# m80-v0_50.net
KiCad netlist of a schematic drawn in EAGLE
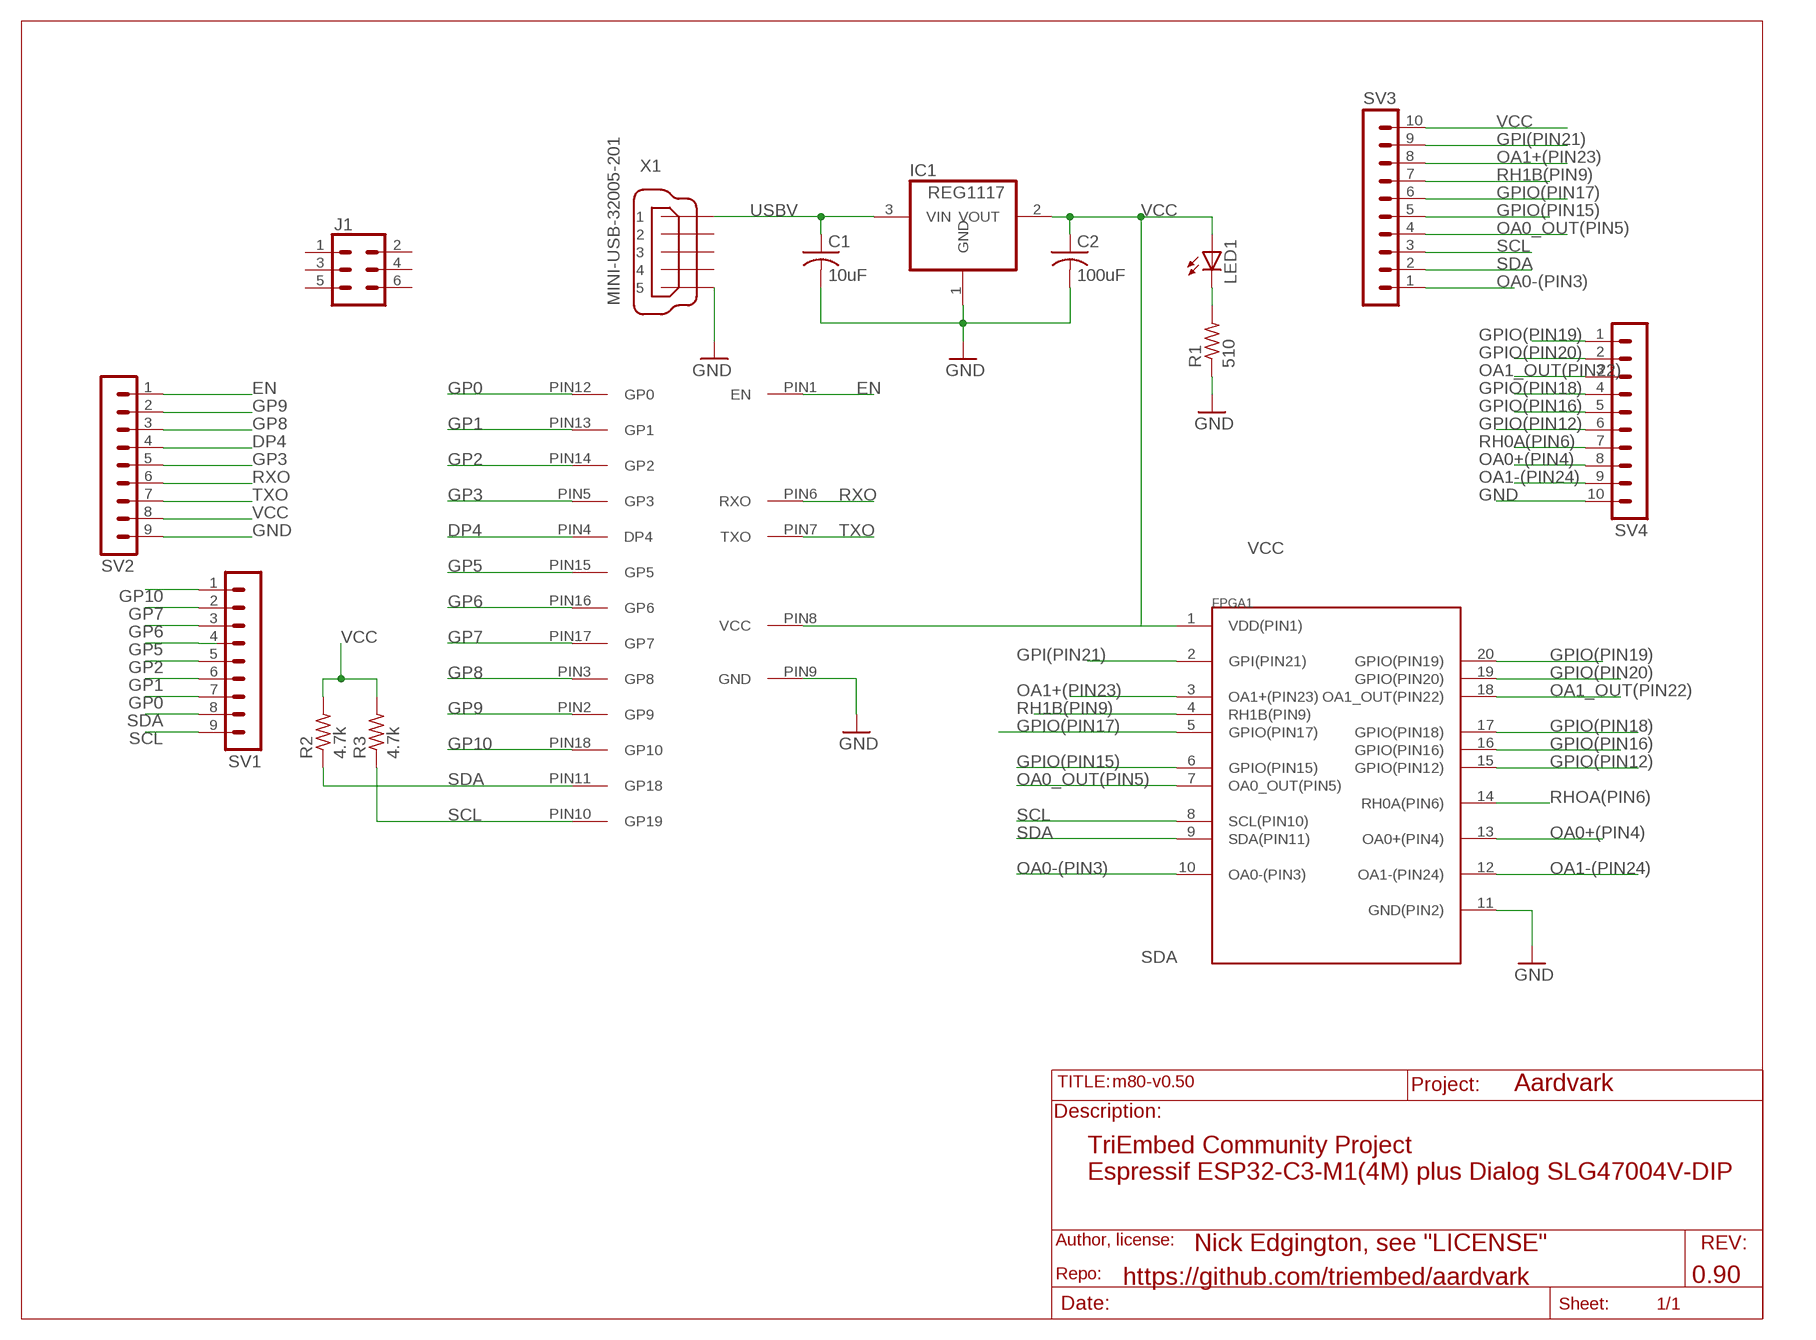
[diagram p0: schematic, sheet 1]

(export (version "E")
  (design (tool "Eeschema 10.0.6"))
  (components
    (comp (ref "C1")
      (value "10uF")
      (footprint "eagle-import:C0805")
      (libsource (lib "eagle-import") (part "C-USC0805"))
    )
    (comp (ref "C2")
      (value "100uF")
      (footprint "eagle-import:C1206")
      (libsource (lib "eagle-import") (part "C-USC1206"))
    )
    (comp (ref "FPGA1")
      (value "SLG7004V_DIP")
      (footprint "eagle-import:SLG47004V-DIP")
      (libsource (lib "eagle-import") (part "SLG7004V_DIP"))
    )
    (comp (ref "IC1")
      (value "REG1117")
      (footprint "eagle-import:SOT223")
      (libsource (lib "eagle-import") (part "REG1117"))
    )
    (comp (ref "J1")
      (value "CONN_03X2NO_SILK")
      (footprint "eagle-import:2X3-NS")
      (libsource (lib "eagle-import") (part "CONN_03X2NO_SILK"))
    )
    (comp (ref "LED1")
      (value "LEDCHIP-LED0805")
      (footprint "eagle-import:CHIP-LED0805")
      (libsource (lib "eagle-import") (part "LEDCHIP-LED0805"))
    )
    (comp (ref "R1")
      (value "510")
      (footprint "eagle-import:R0805")
      (libsource (lib "eagle-import") (part "R-US_R0805"))
    )
    (comp (ref "R2")
      (value "4.7k")
      (footprint "eagle-import:R0805")
      (libsource (lib "eagle-import") (part "R-US_R0805"))
    )
    (comp (ref "R3")
      (value "4.7k")
      (footprint "eagle-import:R0805")
      (libsource (lib "eagle-import") (part "R-US_R0805"))
    )
    (comp (ref "SV1")
      (value "MA09-1")
      (footprint "eagle-import:MA09-1")
      (libsource (lib "eagle-import") (part "MA09-1"))
    )
    (comp (ref "SV2")
      (value "MA09-1")
      (footprint "eagle-import:MA09-1")
      (libsource (lib "eagle-import") (part "MA09-1"))
    )
    (comp (ref "SV3")
      (value "MA10-1")
      (footprint "eagle-import:MA10-1")
      (libsource (lib "eagle-import") (part "MA10-1"))
    )
    (comp (ref "SV4")
      (value "MA10-1")
      (footprint "eagle-import:MA10-1")
      (libsource (lib "eagle-import") (part "MA10-1"))
    )
    (comp (ref "U$2")
      (value "UNTITLED_ESP32C3")
      (footprint "eagle-import:UNTITLED_ESP32-C3-01M")
      (libsource (lib "eagle-import") (part "UNTITLED_ESP32C3"))
    )
    (comp (ref "X1")
      (value "MINI-USB-32005-201")
      (footprint "eagle-import:32005-201")
      (libsource (lib "eagle-import") (part "MINI-USB-32005-201"))
    )
  )
  (nets
    (net (code "1") (name "/DP4") (class "Default")
      (node (ref "SV2") (pin "4") (pinfunction "4_4") (pintype "passive"))
      (node (ref "U$2") (pin "PIN4") (pinfunction "DP4_PIN4") (pintype "bidirectional"))
    )
    (net (code "2") (name "/EN") (class "Default")
      (node (ref "SV2") (pin "1") (pinfunction "1_1") (pintype "passive"))
      (node (ref "U$2") (pin "PIN1") (pinfunction "EN_PIN1") (pintype "input"))
    )
    (net (code "3") (name "/GP0") (class "Default")
      (node (ref "SV1") (pin "7") (pinfunction "7_7") (pintype "passive"))
      (node (ref "U$2") (pin "PIN12") (pinfunction "GP0_PIN12") (pintype "bidirectional"))
    )
    (net (code "4") (name "/GP1") (class "Default")
      (node (ref "SV1") (pin "6") (pinfunction "6_6") (pintype "passive"))
      (node (ref "U$2") (pin "PIN13") (pinfunction "GP1_PIN13") (pintype "bidirectional"))
    )
    (net (code "5") (name "/GP2") (class "Default")
      (node (ref "SV1") (pin "5") (pinfunction "5_5") (pintype "passive"))
      (node (ref "U$2") (pin "PIN14") (pinfunction "GP2_PIN14") (pintype "bidirectional"))
    )
    (net (code "6") (name "/GP3") (class "Default")
      (node (ref "SV2") (pin "5") (pinfunction "5_5") (pintype "passive"))
      (node (ref "U$2") (pin "PIN5") (pinfunction "GP3_PIN5") (pintype "bidirectional"))
    )
    (net (code "7") (name "/GP5") (class "Default")
      (node (ref "SV1") (pin "4") (pinfunction "4_4") (pintype "passive"))
      (node (ref "U$2") (pin "PIN15") (pinfunction "GP5_PIN15") (pintype "bidirectional"))
    )
    (net (code "8") (name "/GP6") (class "Default")
      (node (ref "SV1") (pin "3") (pinfunction "3_3") (pintype "passive"))
      (node (ref "U$2") (pin "PIN16") (pinfunction "GP6_PIN16") (pintype "bidirectional"))
    )
    (net (code "9") (name "/GP7") (class "Default")
      (node (ref "SV1") (pin "2") (pinfunction "2_2") (pintype "passive"))
      (node (ref "U$2") (pin "PIN17") (pinfunction "GP7_PIN17") (pintype "bidirectional"))
    )
    (net (code "10") (name "/GP8") (class "Default")
      (node (ref "SV2") (pin "3") (pinfunction "3_3") (pintype "passive"))
      (node (ref "U$2") (pin "PIN3") (pinfunction "GP8_PIN3") (pintype "bidirectional"))
    )
    (net (code "11") (name "/GP9") (class "Default")
      (node (ref "SV2") (pin "2") (pinfunction "2_2") (pintype "passive"))
      (node (ref "U$2") (pin "PIN2") (pinfunction "GP9_PIN2") (pintype "bidirectional"))
    )
    (net (code "12") (name "/GP10") (class "Default")
      (node (ref "SV1") (pin "1") (pinfunction "1_1") (pintype "passive"))
      (node (ref "U$2") (pin "PIN18") (pinfunction "GP10_PIN18") (pintype "bidirectional"))
    )
    (net (code "13") (name "/GPI(PIN21)") (class "Default")
      (node (ref "FPGA1") (pin "2") (pinfunction "GPI(PIN21)_2") (pintype "input"))
      (node (ref "SV3") (pin "9") (pinfunction "9_9") (pintype "passive"))
    )
    (net (code "14") (name "/GPIO(PIN12)") (class "Default")
      (node (ref "FPGA1") (pin "15") (pinfunction "GPIO(PIN12)_15") (pintype "bidirectional"))
      (node (ref "SV4") (pin "6") (pinfunction "6_6") (pintype "passive"))
    )
    (net (code "15") (name "/GPIO(PIN15)") (class "Default")
      (node (ref "FPGA1") (pin "6") (pinfunction "GPIO(PIN15)_6") (pintype "bidirectional"))
      (node (ref "SV3") (pin "5") (pinfunction "5_5") (pintype "passive"))
    )
    (net (code "16") (name "/GPIO(PIN16)") (class "Default")
      (node (ref "FPGA1") (pin "16") (pinfunction "GPIO(PIN16)_16") (pintype "bidirectional"))
      (node (ref "SV4") (pin "5") (pinfunction "5_5") (pintype "passive"))
    )
    (net (code "17") (name "/GPIO(PIN17)") (class "Default")
      (node (ref "FPGA1") (pin "5") (pinfunction "GPIO(PIN17)_5") (pintype "bidirectional"))
      (node (ref "SV3") (pin "6") (pinfunction "6_6") (pintype "passive"))
    )
    (net (code "18") (name "/GPIO(PIN18)") (class "Default")
      (node (ref "FPGA1") (pin "17") (pinfunction "GPIO(PIN18)_17") (pintype "input"))
      (node (ref "SV4") (pin "4") (pinfunction "4_4") (pintype "passive"))
    )
    (net (code "19") (name "/GPIO(PIN19)") (class "Default")
      (node (ref "FPGA1") (pin "20") (pinfunction "GPIO(PIN19)_20") (pintype "bidirectional"))
      (node (ref "SV4") (pin "1") (pinfunction "1_1") (pintype "passive"))
    )
    (net (code "20") (name "/GPIO(PIN20)") (class "Default")
      (node (ref "FPGA1") (pin "19") (pinfunction "GPIO(PIN20)_19") (pintype "bidirectional"))
      (node (ref "SV4") (pin "2") (pinfunction "2_2") (pintype "passive"))
    )
    (net (code "21") (name "/OA0+(PIN4)") (class "Default")
      (node (ref "FPGA1") (pin "13") (pinfunction "OA0+(PIN4)_13") (pintype "bidirectional"))
      (node (ref "SV4") (pin "8") (pinfunction "8_8") (pintype "passive"))
    )
    (net (code "22") (name "/OA0-(PIN3)") (class "Default")
      (node (ref "FPGA1") (pin "10") (pinfunction "OA0-(PIN3)_10") (pintype "open_collector"))
      (node (ref "SV3") (pin "1") (pinfunction "1_1") (pintype "passive"))
    )
    (net (code "23") (name "/OA0_OUT(PIN5)") (class "Default")
      (node (ref "FPGA1") (pin "7") (pinfunction "OA0_OUT(PIN5)_7") (pintype "bidirectional"))
      (node (ref "SV3") (pin "4") (pinfunction "4_4") (pintype "passive"))
    )
    (net (code "24") (name "/OA1+(PIN23)") (class "Default")
      (node (ref "FPGA1") (pin "3") (pinfunction "OA1+(PIN23)_3") (pintype "bidirectional"))
      (node (ref "SV3") (pin "8") (pinfunction "8_8") (pintype "passive"))
    )
    (net (code "25") (name "/OA1-(PIN24)") (class "Default")
      (node (ref "FPGA1") (pin "12") (pinfunction "OA1-(PIN24)_12") (pintype "bidirectional"))
      (node (ref "SV4") (pin "9") (pinfunction "9_9") (pintype "passive"))
    )
    (net (code "26") (name "/OA1_OUT(PIN22)") (class "Default")
      (node (ref "FPGA1") (pin "18") (pinfunction "OA1_OUT(PIN22)_18") (pintype "bidirectional"))
      (node (ref "SV4") (pin "3") (pinfunction "3_3") (pintype "passive"))
    )
    (net (code "27") (name "/RH0A(PIN6)") (class "Default")
      (node (ref "SV4") (pin "7") (pinfunction "7_7") (pintype "passive"))
    )
    (net (code "28") (name "/RH1B(PIN9)") (class "Default")
      (node (ref "FPGA1") (pin "4") (pinfunction "RH1B(PIN9)_4") (pintype "passive"))
      (node (ref "SV3") (pin "7") (pinfunction "7_7") (pintype "passive"))
    )
    (net (code "29") (name "/RHOA(PIN6)") (class "Default")
      (node (ref "FPGA1") (pin "14") (pinfunction "RH0A(PIN6)_14") (pintype "passive"))
    )
    (net (code "30") (name "/RXO") (class "Default")
      (node (ref "SV2") (pin "6") (pinfunction "6_6") (pintype "passive"))
      (node (ref "U$2") (pin "PIN6") (pinfunction "RXO_PIN6") (pintype "bidirectional"))
    )
    (net (code "31") (name "/SCL") (class "Default")
      (node (ref "FPGA1") (pin "8") (pinfunction "SCL(PIN10)_8") (pintype "bidirectional"))
      (node (ref "R3") (pin "1") (pinfunction "1_1") (pintype "passive"))
      (node (ref "SV1") (pin "9") (pinfunction "9_9") (pintype "passive"))
      (node (ref "SV3") (pin "3") (pinfunction "3_3") (pintype "passive"))
      (node (ref "U$2") (pin "PIN10") (pinfunction "GP19_PIN10") (pintype "bidirectional"))
    )
    (net (code "32") (name "/SDA") (class "Default")
      (node (ref "FPGA1") (pin "9") (pinfunction "SDA(PIN11)_9") (pintype "bidirectional"))
      (node (ref "R2") (pin "1") (pinfunction "1_1") (pintype "passive"))
      (node (ref "SV1") (pin "8") (pinfunction "8_8") (pintype "passive"))
      (node (ref "SV3") (pin "2") (pinfunction "2_2") (pintype "passive"))
      (node (ref "U$2") (pin "PIN11") (pinfunction "GP18_PIN11") (pintype "bidirectional"))
    )
    (net (code "33") (name "/TXO") (class "Default")
      (node (ref "SV2") (pin "7") (pinfunction "7_7") (pintype "passive"))
      (node (ref "U$2") (pin "PIN7") (pinfunction "TXO_PIN7") (pintype "bidirectional"))
    )
    (net (code "34") (name "/USBV") (class "Default")
      (node (ref "C1") (pin "1") (pinfunction "1_1") (pintype "passive"))
      (node (ref "IC1") (pin "3") (pinfunction "VIN_3") (pintype "input"))
      (node (ref "X1") (pin "1") (pinfunction "1_1") (pintype "passive"))
    )
    (net (code "35") (name "/VCC") (class "Default")
      (node (ref "C2") (pin "1") (pinfunction "1_1") (pintype "passive"))
      (node (ref "FPGA1") (pin "1") (pinfunction "VDD(PIN1)_1") (pintype "power_in"))
      (node (ref "IC1") (pin "2") (pinfunction "VOUT_2") (pintype "output"))
      (node (ref "LED1") (pin "A") (pinfunction "A_A") (pintype "passive"))
      (node (ref "R2") (pin "2") (pinfunction "2_2") (pintype "passive"))
      (node (ref "R3") (pin "2") (pinfunction "2_2") (pintype "passive"))
      (node (ref "SV2") (pin "8") (pinfunction "8_8") (pintype "passive"))
      (node (ref "SV3") (pin "10") (pinfunction "10_10") (pintype "passive"))
      (node (ref "U$2") (pin "PIN8") (pinfunction "VCC_PIN8") (pintype "power_in"))
    )
    (net (code "36") (name "GND") (class "Default")
      (node (ref "C1") (pin "2") (pinfunction "2_2") (pintype "passive"))
      (node (ref "C2") (pin "2") (pinfunction "2_2") (pintype "passive"))
      (node (ref "FPGA1") (pin "11") (pinfunction "GND(PIN2)_11") (pintype "power_in"))
      (node (ref "IC1") (pin "1") (pinfunction "GND_1") (pintype "power_in"))
      (node (ref "R1") (pin "1") (pinfunction "1_1") (pintype "passive"))
      (node (ref "SV2") (pin "9") (pinfunction "9_9") (pintype "passive"))
      (node (ref "SV4") (pin "10") (pinfunction "10_10") (pintype "passive"))
      (node (ref "U$2") (pin "PIN9") (pinfunction "GND_PIN9") (pintype "power_in"))
      (node (ref "X1") (pin "5") (pinfunction "5_5") (pintype "passive"))
    )
    (net (code "37") (name "Net-(LED1-PadC)") (class "Default")
      (node (ref "LED1") (pin "C") (pinfunction "C_C") (pintype "passive"))
      (node (ref "R1") (pin "2") (pinfunction "2_2") (pintype "passive"))
    )
    (net (code "38") (name "unconnected-(J1-Pad1)") (class "Default")
      (node (ref "J1") (pin "1") (pinfunction "1_1") (pintype "bidirectional"))
    )
    (net (code "39") (name "unconnected-(J1-Pad2)") (class "Default")
      (node (ref "J1") (pin "2") (pinfunction "2_2") (pintype "bidirectional"))
    )
    (net (code "40") (name "unconnected-(J1-Pad3)") (class "Default")
      (node (ref "J1") (pin "3") (pinfunction "3_3") (pintype "bidirectional"))
    )
    (net (code "41") (name "unconnected-(J1-Pad4)") (class "Default")
      (node (ref "J1") (pin "4") (pinfunction "4_4") (pintype "bidirectional"))
    )
    (net (code "42") (name "unconnected-(J1-Pad5)") (class "Default")
      (node (ref "J1") (pin "5") (pinfunction "5_5") (pintype "bidirectional"))
    )
    (net (code "43") (name "unconnected-(J1-Pad6)") (class "Default")
      (node (ref "J1") (pin "6") (pinfunction "6_6") (pintype "bidirectional"))
    )
    (net (code "44") (name "unconnected-(X1-Pad2)") (class "Default")
      (node (ref "X1") (pin "2") (pinfunction "2_2") (pintype "passive"))
    )
    (net (code "45") (name "unconnected-(X1-Pad3)") (class "Default")
      (node (ref "X1") (pin "3") (pinfunction "3_3") (pintype "passive"))
    )
    (net (code "46") (name "unconnected-(X1-Pad4)") (class "Default")
      (node (ref "X1") (pin "4") (pinfunction "4_4") (pintype "passive"))
    )
  )
)
